# OR_Mod_PCB_v002.net
KiCad netlist of a schematic drawn in EAGLE
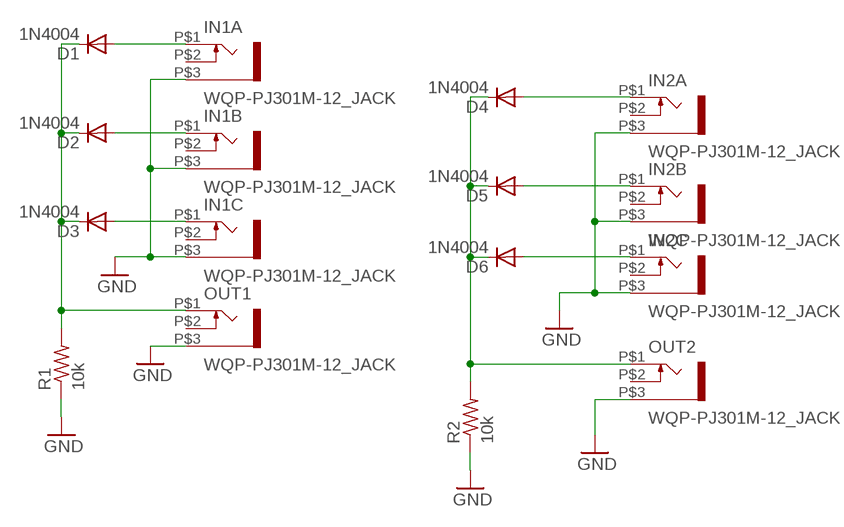
[diagram p0: schematic, sheet 1]

(export (version "E")
  (design (tool "Eeschema 10.0.6"))
  (components
    (comp (ref "D1")
      (value "1N4004")
      (footprint "eagle-import:DO41-10")
      (libsource (lib "eagle-import") (part "1N4004"))
    )
    (comp (ref "D2")
      (value "1N4004")
      (footprint "eagle-import:DO41-10")
      (libsource (lib "eagle-import") (part "1N4004"))
    )
    (comp (ref "D3")
      (value "1N4004")
      (footprint "eagle-import:DO41-10")
      (libsource (lib "eagle-import") (part "1N4004"))
    )
    (comp (ref "D4")
      (value "1N4004")
      (footprint "eagle-import:DO41-10")
      (libsource (lib "eagle-import") (part "1N4004"))
    )
    (comp (ref "D5")
      (value "1N4004")
      (footprint "eagle-import:DO41-10")
      (libsource (lib "eagle-import") (part "1N4004"))
    )
    (comp (ref "D6")
      (value "1N4004")
      (footprint "eagle-import:DO41-10")
      (libsource (lib "eagle-import") (part "1N4004"))
    )
    (comp (ref "IN1A")
      (value "WQP-PJ301M-12_JACK")
      (footprint "eagle-import:WQP-PJ301M-12_JACK")
      (libsource (lib "eagle-import") (part "WQP-PJ301M-12_JACK"))
    )
    (comp (ref "IN1B")
      (value "WQP-PJ301M-12_JACK")
      (footprint "eagle-import:WQP-PJ301M-12_JACK")
      (libsource (lib "eagle-import") (part "WQP-PJ301M-12_JACK"))
    )
    (comp (ref "IN1C")
      (value "WQP-PJ301M-12_JACK")
      (footprint "eagle-import:WQP-PJ301M-12_JACK")
      (libsource (lib "eagle-import") (part "WQP-PJ301M-12_JACK"))
    )
    (comp (ref "IN2A")
      (value "WQP-PJ301M-12_JACK")
      (footprint "eagle-import:WQP-PJ301M-12_JACK")
      (libsource (lib "eagle-import") (part "WQP-PJ301M-12_JACK"))
    )
    (comp (ref "IN2B")
      (value "WQP-PJ301M-12_JACK")
      (footprint "eagle-import:WQP-PJ301M-12_JACK")
      (libsource (lib "eagle-import") (part "WQP-PJ301M-12_JACK"))
    )
    (comp (ref "IN2C")
      (value "WQP-PJ301M-12_JACK")
      (footprint "eagle-import:WQP-PJ301M-12_JACK")
      (libsource (lib "eagle-import") (part "WQP-PJ301M-12_JACK"))
    )
    (comp (ref "OUT1")
      (value "WQP-PJ301M-12_JACK")
      (footprint "eagle-import:WQP-PJ301M-12_JACK")
      (libsource (lib "eagle-import") (part "WQP-PJ301M-12_JACK"))
    )
    (comp (ref "OUT2")
      (value "WQP-PJ301M-12_JACK")
      (footprint "eagle-import:WQP-PJ301M-12_JACK")
      (libsource (lib "eagle-import") (part "WQP-PJ301M-12_JACK"))
    )
    (comp (ref "R1")
      (value "10k")
      (footprint "eagle-import:0204_7")
      (libsource (lib "eagle-import") (part "R-US_0204/7"))
    )
    (comp (ref "R2")
      (value "10k")
      (footprint "eagle-import:0204_7")
      (libsource (lib "eagle-import") (part "R-US_0204/7"))
    )
  )
  (nets
    (net (code "1") (name "GND") (class "Default")
      (node (ref "IN1A") (pin "P$3") (pinfunction "1_P$3") (pintype "passive"))
      (node (ref "IN1B") (pin "P$3") (pinfunction "1_P$3") (pintype "passive"))
      (node (ref "IN1C") (pin "P$3") (pinfunction "1_P$3") (pintype "passive"))
      (node (ref "IN2A") (pin "P$3") (pinfunction "1_P$3") (pintype "passive"))
      (node (ref "IN2B") (pin "P$3") (pinfunction "1_P$3") (pintype "passive"))
      (node (ref "IN2C") (pin "P$3") (pinfunction "1_P$3") (pintype "passive"))
      (node (ref "OUT1") (pin "P$3") (pinfunction "1_P$3") (pintype "passive"))
      (node (ref "OUT2") (pin "P$3") (pinfunction "1_P$3") (pintype "passive"))
      (node (ref "R1") (pin "1") (pinfunction "1_1") (pintype "passive"))
      (node (ref "R2") (pin "1") (pinfunction "1_1") (pintype "passive"))
    )
    (net (code "2") (name "Net-(IN1A-2)") (class "Default")
      (node (ref "D1") (pin "A") (pinfunction "A_A") (pintype "passive"))
      (node (ref "IN1A") (pin "P$1") (pinfunction "2_P$1") (pintype "passive"))
    )
    (net (code "3") (name "Net-(IN1B-2)") (class "Default")
      (node (ref "D2") (pin "A") (pinfunction "A_A") (pintype "passive"))
      (node (ref "IN1B") (pin "P$1") (pinfunction "2_P$1") (pintype "passive"))
    )
    (net (code "4") (name "Net-(IN1C-2)") (class "Default")
      (node (ref "D3") (pin "A") (pinfunction "A_A") (pintype "passive"))
      (node (ref "IN1C") (pin "P$1") (pinfunction "2_P$1") (pintype "passive"))
    )
    (net (code "5") (name "Net-(IN2A-2)") (class "Default")
      (node (ref "D4") (pin "A") (pinfunction "A_A") (pintype "passive"))
      (node (ref "IN2A") (pin "P$1") (pinfunction "2_P$1") (pintype "passive"))
    )
    (net (code "6") (name "Net-(IN2B-2)") (class "Default")
      (node (ref "D5") (pin "A") (pinfunction "A_A") (pintype "passive"))
      (node (ref "IN2B") (pin "P$1") (pinfunction "2_P$1") (pintype "passive"))
    )
    (net (code "7") (name "Net-(IN2C-2)") (class "Default")
      (node (ref "D6") (pin "A") (pinfunction "A_A") (pintype "passive"))
      (node (ref "IN2C") (pin "P$1") (pinfunction "2_P$1") (pintype "passive"))
    )
    (net (code "8") (name "Net-(OUT1-2)") (class "Default")
      (node (ref "D1") (pin "C") (pinfunction "C_C") (pintype "passive"))
      (node (ref "D2") (pin "C") (pinfunction "C_C") (pintype "passive"))
      (node (ref "D3") (pin "C") (pinfunction "C_C") (pintype "passive"))
      (node (ref "OUT1") (pin "P$1") (pinfunction "2_P$1") (pintype "passive"))
      (node (ref "R1") (pin "2") (pinfunction "2_2") (pintype "passive"))
    )
    (net (code "9") (name "Net-(OUT2-2)") (class "Default")
      (node (ref "D4") (pin "C") (pinfunction "C_C") (pintype "passive"))
      (node (ref "D5") (pin "C") (pinfunction "C_C") (pintype "passive"))
      (node (ref "D6") (pin "C") (pinfunction "C_C") (pintype "passive"))
      (node (ref "OUT2") (pin "P$1") (pinfunction "2_P$1") (pintype "passive"))
      (node (ref "R2") (pin "2") (pinfunction "2_2") (pintype "passive"))
    )
    (net (code "10") (name "unconnected-(IN1A-3-PadP$2)") (class "Default")
      (node (ref "IN1A") (pin "P$2") (pinfunction "3_P$2") (pintype "passive"))
    )
    (net (code "11") (name "unconnected-(IN1B-3-PadP$2)") (class "Default")
      (node (ref "IN1B") (pin "P$2") (pinfunction "3_P$2") (pintype "passive"))
    )
    (net (code "12") (name "unconnected-(IN1C-3-PadP$2)") (class "Default")
      (node (ref "IN1C") (pin "P$2") (pinfunction "3_P$2") (pintype "passive"))
    )
    (net (code "13") (name "unconnected-(IN2A-3-PadP$2)") (class "Default")
      (node (ref "IN2A") (pin "P$2") (pinfunction "3_P$2") (pintype "passive"))
    )
    (net (code "14") (name "unconnected-(IN2B-3-PadP$2)") (class "Default")
      (node (ref "IN2B") (pin "P$2") (pinfunction "3_P$2") (pintype "passive"))
    )
    (net (code "15") (name "unconnected-(IN2C-3-PadP$2)") (class "Default")
      (node (ref "IN2C") (pin "P$2") (pinfunction "3_P$2") (pintype "passive"))
    )
    (net (code "16") (name "unconnected-(OUT1-3-PadP$2)") (class "Default")
      (node (ref "OUT1") (pin "P$2") (pinfunction "3_P$2") (pintype "passive"))
    )
    (net (code "17") (name "unconnected-(OUT2-3-PadP$2)") (class "Default")
      (node (ref "OUT2") (pin "P$2") (pinfunction "3_P$2") (pintype "passive"))
    )
  )
)
